# Shield_Programmer.net
KiCad netlist of a schematic drawn in EAGLE
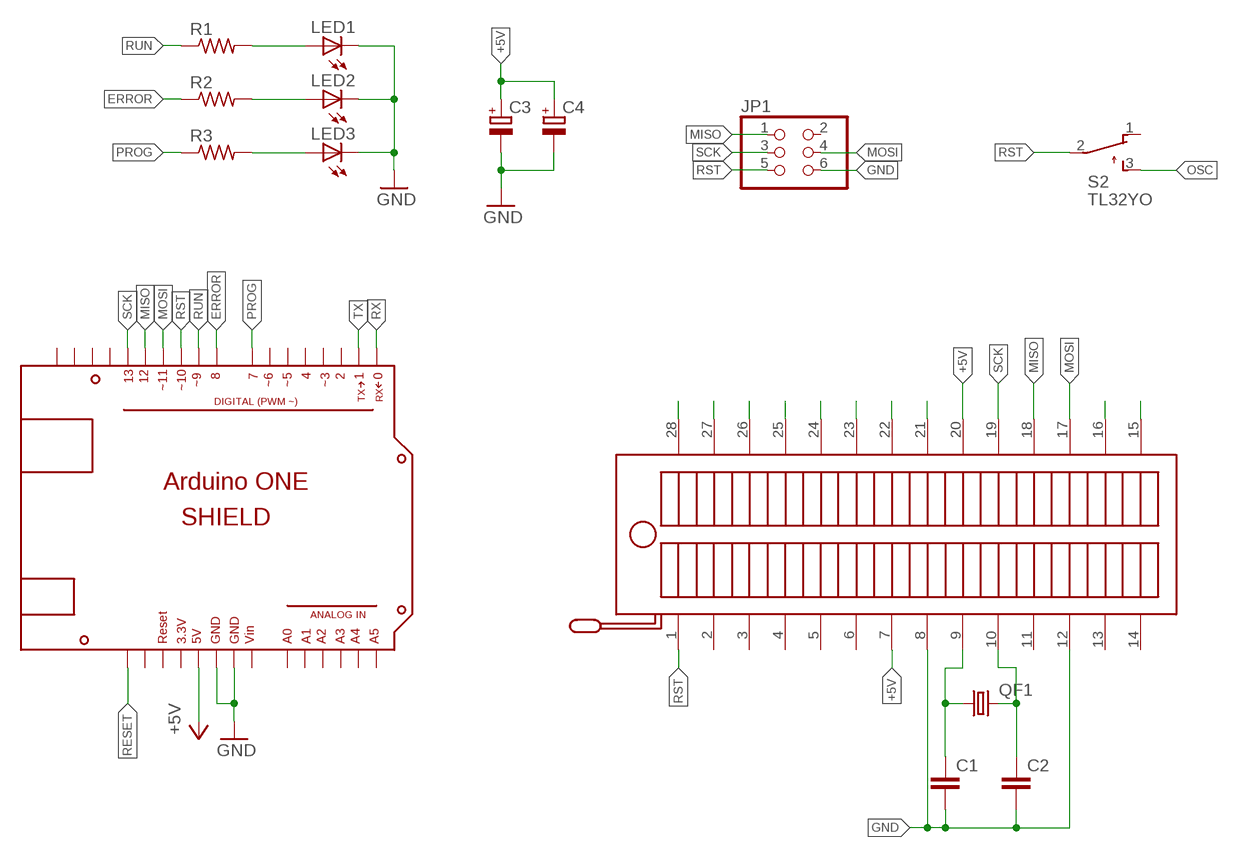
[diagram p0: schematic, sheet 1]

(export (version "E")
  (design (tool "Eeschema 10.0.6"))
  (components
    (comp (ref "C1")
      (value "C5/2.5")
      (footprint "eagle-import:C5B2.5")
      (libsource (lib "eagle-import") (part "C5/2.5"))
    )
    (comp (ref "C2")
      (value "C5/2.5")
      (footprint "eagle-import:C5B2.5")
      (libsource (lib "eagle-import") (part "C5/2.5"))
    )
    (comp (ref "C3")
      (value "CPOL-EUE2.5-7")
      (footprint "eagle-import:E2,5-7")
      (libsource (lib "eagle-import") (part "CPOL-EUE2.5-7"))
    )
    (comp (ref "C4")
      (value "CPOL-EUE2.5-7")
      (footprint "eagle-import:E2,5-7")
      (libsource (lib "eagle-import") (part "CPOL-EUE2.5-7"))
    )
    (comp (ref "JP1")
      (value "PINHD-2X3")
      (footprint "eagle-import:2X03")
      (libsource (lib "eagle-import") (part "PINHD-2X3"))
    )
    (comp (ref "LED1")
      (value "LED3MM")
      (footprint "eagle-import:LED3MM")
      (libsource (lib "eagle-import") (part "LED3MM"))
    )
    (comp (ref "LED2")
      (value "LED3MM")
      (footprint "eagle-import:LED3MM")
      (libsource (lib "eagle-import") (part "LED3MM"))
    )
    (comp (ref "LED3")
      (value "LED3MM")
      (footprint "eagle-import:LED3MM")
      (libsource (lib "eagle-import") (part "LED3MM"))
    )
    (comp (ref "QF1")
      (value "CRYSTALHC49U-V")
      (footprint "eagle-import:HC49U-V")
      (fields (field (name "OC_FARNELL") "1666969"))
      (libsource (lib "eagle-import") (part "CRYSTALHC49U-V"))
    )
    (comp (ref "R1")
      (value "R-US_0204/7")
      (footprint "eagle-import:0204_7")
      (libsource (lib "eagle-import") (part "R-US_0204/7"))
    )
    (comp (ref "R2")
      (value "R-US_0204/7")
      (footprint "eagle-import:0204_7")
      (libsource (lib "eagle-import") (part "R-US_0204/7"))
    )
    (comp (ref "R3")
      (value "R-US_0204/7")
      (footprint "eagle-import:0204_7")
      (libsource (lib "eagle-import") (part "R-US_0204/7"))
    )
    (comp (ref "S2")
      (value "TL32YO")
      (footprint "eagle-import:TL3XYO")
      (libsource (lib "eagle-import") (part "TL32YO"))
    )
    (comp (ref "U$2")
      (value "ZIF-28")
      (footprint "eagle-import:ZIF-28")
      (libsource (lib "eagle-import") (part "ZIF-28"))
    )
    (comp (ref "U$3")
      (value "SHIELD")
      (footprint "eagle-import:SHIELD")
      (libsource (lib "eagle-import") (part "SHIELD"))
    )
  )
  (nets
    (net (code "1") (name "+5V") (class "Default")
      (node (ref "C3") (pin "+") (pinfunction "+_+") (pintype "passive"))
      (node (ref "C4") (pin "+") (pinfunction "+_+") (pintype "passive"))
      (node (ref "U$2") (pin "20") (pinfunction "PIN20_20") (pintype "bidirectional"))
      (node (ref "U$2") (pin "7") (pinfunction "PIN7_7") (pintype "bidirectional"))
      (node (ref "U$3") (pin "5V") (pinfunction "5V_5V") (pintype "bidirectional"))
    )
    (net (code "2") (name "ERROR") (class "Default")
      (node (ref "R2") (pin "1") (pinfunction "1_1") (pintype "passive"))
      (node (ref "U$3") (pin "8") (pinfunction "8_8") (pintype "bidirectional"))
    )
    (net (code "3") (name "GND") (class "Default")
      (node (ref "C1") (pin "2") (pinfunction "2_2") (pintype "passive"))
      (node (ref "C2") (pin "2") (pinfunction "2_2") (pintype "passive"))
      (node (ref "C3") (pin "-") (pinfunction "-_-") (pintype "passive"))
      (node (ref "C4") (pin "-") (pinfunction "-_-") (pintype "passive"))
      (node (ref "JP1") (pin "6") (pinfunction "6_6") (pintype "passive"))
      (node (ref "LED1") (pin "K") (pinfunction "C_K") (pintype "passive"))
      (node (ref "LED2") (pin "K") (pinfunction "C_K") (pintype "passive"))
      (node (ref "LED3") (pin "K") (pinfunction "C_K") (pintype "passive"))
      (node (ref "U$2") (pin "12") (pinfunction "PIN12_12") (pintype "bidirectional"))
      (node (ref "U$2") (pin "8") (pinfunction "PIN8_8") (pintype "bidirectional"))
      (node (ref "U$3") (pin "GND1") (pinfunction "GND1_GND1") (pintype "bidirectional"))
      (node (ref "U$3") (pin "GND2") (pinfunction "GND2_GND2") (pintype "bidirectional"))
    )
    (net (code "4") (name "MISO") (class "Default")
      (node (ref "JP1") (pin "1") (pinfunction "1_1") (pintype "passive"))
      (node (ref "U$2") (pin "18") (pinfunction "PIN18_18") (pintype "bidirectional"))
      (node (ref "U$3") (pin "12") (pinfunction "12_12") (pintype "bidirectional"))
    )
    (net (code "5") (name "MOSI") (class "Default")
      (node (ref "JP1") (pin "4") (pinfunction "4_4") (pintype "passive"))
      (node (ref "U$2") (pin "17") (pinfunction "PIN17_17") (pintype "bidirectional"))
      (node (ref "U$3") (pin "11") (pinfunction "11_11") (pintype "bidirectional"))
    )
    (net (code "6") (name "Net-(LED1-PadA)") (class "Default")
      (node (ref "LED1") (pin "A") (pinfunction "A_A") (pintype "passive"))
      (node (ref "R1") (pin "2") (pinfunction "2_2") (pintype "passive"))
    )
    (net (code "7") (name "Net-(LED2-PadA)") (class "Default")
      (node (ref "LED2") (pin "A") (pinfunction "A_A") (pintype "passive"))
      (node (ref "R2") (pin "2") (pinfunction "2_2") (pintype "passive"))
    )
    (net (code "8") (name "Net-(LED3-PadA)") (class "Default")
      (node (ref "LED3") (pin "A") (pinfunction "A_A") (pintype "passive"))
      (node (ref "R3") (pin "2") (pinfunction "2_2") (pintype "passive"))
    )
    (net (code "9") (name "Net-(U$2-PIN10)") (class "Default")
      (node (ref "C2") (pin "1") (pinfunction "1_1") (pintype "passive"))
      (node (ref "QF1") (pin "2") (pinfunction "2_2") (pintype "passive"))
      (node (ref "U$2") (pin "10") (pinfunction "PIN10_10") (pintype "bidirectional"))
    )
    (net (code "10") (name "OSC") (class "Default")
      (node (ref "C1") (pin "1") (pinfunction "1_1") (pintype "passive"))
      (node (ref "QF1") (pin "1") (pinfunction "1_1") (pintype "passive"))
      (node (ref "S2") (pin "3") (pinfunction "S_3") (pintype "passive"))
      (node (ref "U$2") (pin "9") (pinfunction "PIN9_9") (pintype "bidirectional"))
    )
    (net (code "11") (name "PROG") (class "Default")
      (node (ref "R3") (pin "1") (pinfunction "1_1") (pintype "passive"))
      (node (ref "U$3") (pin "7") (pinfunction "7_7") (pintype "bidirectional"))
    )
    (net (code "12") (name "RESET") (class "Default")
      (node (ref "U$3") (pin "NONE") (pinfunction "NONE_NONE") (pintype "bidirectional"))
    )
    (net (code "13") (name "RST") (class "Default")
      (node (ref "JP1") (pin "5") (pinfunction "5_5") (pintype "passive"))
      (node (ref "S2") (pin "2") (pinfunction "P_2") (pintype "passive"))
      (node (ref "U$2") (pin "1") (pinfunction "PIN1_1") (pintype "bidirectional"))
      (node (ref "U$3") (pin "10") (pinfunction "10_10") (pintype "bidirectional"))
    )
    (net (code "14") (name "RUN") (class "Default")
      (node (ref "R1") (pin "1") (pinfunction "1_1") (pintype "passive"))
      (node (ref "U$3") (pin "9") (pinfunction "9_9") (pintype "bidirectional"))
    )
    (net (code "15") (name "RX") (class "Default")
      (node (ref "U$3") (pin "0") (pinfunction "0_0") (pintype "bidirectional"))
    )
    (net (code "16") (name "SCK") (class "Default")
      (node (ref "JP1") (pin "3") (pinfunction "3_3") (pintype "passive"))
      (node (ref "U$2") (pin "19") (pinfunction "PIN19_19") (pintype "bidirectional"))
      (node (ref "U$3") (pin "13") (pinfunction "13_13") (pintype "bidirectional"))
    )
    (net (code "17") (name "TX") (class "Default")
      (node (ref "U$3") (pin "1") (pinfunction "1_1") (pintype "bidirectional"))
    )
    (net (code "18") (name "unconnected-(JP1-Pad2)") (class "Default")
      (node (ref "JP1") (pin "2") (pinfunction "2_2") (pintype "passive"))
    )
    (net (code "19") (name "unconnected-(S2-O-Pad1)") (class "Default")
      (node (ref "S2") (pin "1") (pinfunction "O_1") (pintype "passive"))
    )
    (net (code "20") (name "unconnected-(U$2-PIN2-Pad2)") (class "Default")
      (node (ref "U$2") (pin "2") (pinfunction "PIN2_2") (pintype "bidirectional"))
    )
    (net (code "21") (name "unconnected-(U$2-PIN3-Pad3)") (class "Default")
      (node (ref "U$2") (pin "3") (pinfunction "PIN3_3") (pintype "bidirectional"))
    )
    (net (code "22") (name "unconnected-(U$2-PIN4-Pad4)") (class "Default")
      (node (ref "U$2") (pin "4") (pinfunction "PIN4_4") (pintype "bidirectional"))
    )
    (net (code "23") (name "unconnected-(U$2-PIN5-Pad5)") (class "Default")
      (node (ref "U$2") (pin "5") (pinfunction "PIN5_5") (pintype "bidirectional"))
    )
    (net (code "24") (name "unconnected-(U$2-PIN6-Pad6)") (class "Default")
      (node (ref "U$2") (pin "6") (pinfunction "PIN6_6") (pintype "bidirectional"))
    )
    (net (code "25") (name "unconnected-(U$2-PIN11-Pad11)") (class "Default")
      (node (ref "U$2") (pin "11") (pinfunction "PIN11_11") (pintype "bidirectional"))
    )
    (net (code "26") (name "unconnected-(U$2-PIN13-Pad13)") (class "Default")
      (node (ref "U$2") (pin "13") (pinfunction "PIN13_13") (pintype "bidirectional"))
    )
    (net (code "27") (name "unconnected-(U$2-PIN14-Pad14)") (class "Default")
      (node (ref "U$2") (pin "14") (pinfunction "PIN14_14") (pintype "bidirectional"))
    )
    (net (code "28") (name "unconnected-(U$2-PIN15-Pad15)") (class "Default")
      (node (ref "U$2") (pin "15") (pinfunction "PIN15_15") (pintype "bidirectional"))
    )
    (net (code "29") (name "unconnected-(U$2-PIN16-Pad16)") (class "Default")
      (node (ref "U$2") (pin "16") (pinfunction "PIN16_16") (pintype "bidirectional"))
    )
    (net (code "30") (name "unconnected-(U$2-PIN21-Pad21)") (class "Default")
      (node (ref "U$2") (pin "21") (pinfunction "PIN21_21") (pintype "bidirectional"))
    )
    (net (code "31") (name "unconnected-(U$2-PIN22-Pad22)") (class "Default")
      (node (ref "U$2") (pin "22") (pinfunction "PIN22_22") (pintype "bidirectional"))
    )
    (net (code "32") (name "unconnected-(U$2-PIN23-Pad23)") (class "Default")
      (node (ref "U$2") (pin "23") (pinfunction "PIN23_23") (pintype "bidirectional"))
    )
    (net (code "33") (name "unconnected-(U$2-PIN24-Pad24)") (class "Default")
      (node (ref "U$2") (pin "24") (pinfunction "PIN24_24") (pintype "bidirectional"))
    )
    (net (code "34") (name "unconnected-(U$2-PIN25-Pad25)") (class "Default")
      (node (ref "U$2") (pin "25") (pinfunction "PIN25_25") (pintype "bidirectional"))
    )
    (net (code "35") (name "unconnected-(U$2-PIN26-Pad26)") (class "Default")
      (node (ref "U$2") (pin "26") (pinfunction "PIN26_26") (pintype "bidirectional"))
    )
    (net (code "36") (name "unconnected-(U$2-PIN27-Pad27)") (class "Default")
      (node (ref "U$2") (pin "27") (pinfunction "PIN27_27") (pintype "bidirectional"))
    )
    (net (code "37") (name "unconnected-(U$2-PIN28-Pad28)") (class "Default")
      (node (ref "U$2") (pin "28") (pinfunction "PIN28_28") (pintype "bidirectional"))
    )
    (net (code "38") (name "unconnected-(U$3-Pad2)") (class "Default")
      (node (ref "U$3") (pin "2") (pinfunction "2_2") (pintype "bidirectional"))
    )
    (net (code "39") (name "unconnected-(U$3-Pad3)") (class "Default")
      (node (ref "U$3") (pin "3") (pinfunction "3_3") (pintype "bidirectional"))
    )
    (net (code "40") (name "unconnected-(U$3-Pad3.3V)") (class "Default")
      (node (ref "U$3") (pin "3.3V") (pinfunction "3.3V_3.3V") (pintype "bidirectional"))
    )
    (net (code "41") (name "unconnected-(U$3-Pad4)") (class "Default")
      (node (ref "U$3") (pin "4") (pinfunction "4_4") (pintype "bidirectional"))
    )
    (net (code "42") (name "unconnected-(U$3-Pad5)") (class "Default")
      (node (ref "U$3") (pin "5") (pinfunction "5_5") (pintype "bidirectional"))
    )
    (net (code "43") (name "unconnected-(U$3-Pad6)") (class "Default")
      (node (ref "U$3") (pin "6") (pinfunction "6_6") (pintype "bidirectional"))
    )
    (net (code "44") (name "unconnected-(U$3-Pad14)") (class "Default")
      (node (ref "U$3") (pin "14") (pinfunction "14_14") (pintype "bidirectional"))
    )
    (net (code "45") (name "unconnected-(U$3-Pad15)") (class "Default")
      (node (ref "U$3") (pin "15") (pinfunction "15_15") (pintype "bidirectional"))
    )
    (net (code "46") (name "unconnected-(U$3-Pad16)") (class "Default")
      (node (ref "U$3") (pin "16") (pinfunction "16_16") (pintype "bidirectional"))
    )
    (net (code "47") (name "unconnected-(U$3-Pad17)") (class "Default")
      (node (ref "U$3") (pin "17") (pinfunction "17_17") (pintype "bidirectional"))
    )
    (net (code "48") (name "unconnected-(U$3-PadA0)") (class "Default")
      (node (ref "U$3") (pin "A0") (pinfunction "A0_A0") (pintype "bidirectional"))
    )
    (net (code "49") (name "unconnected-(U$3-PadA1)") (class "Default")
      (node (ref "U$3") (pin "A1") (pinfunction "A1_A1") (pintype "bidirectional"))
    )
    (net (code "50") (name "unconnected-(U$3-PadA2)") (class "Default")
      (node (ref "U$3") (pin "A2") (pinfunction "A2_A2") (pintype "bidirectional"))
    )
    (net (code "51") (name "unconnected-(U$3-PadA3)") (class "Default")
      (node (ref "U$3") (pin "A3") (pinfunction "A3_A3") (pintype "bidirectional"))
    )
    (net (code "52") (name "unconnected-(U$3-PadA4)") (class "Default")
      (node (ref "U$3") (pin "A4") (pinfunction "A4_A4") (pintype "bidirectional"))
    )
    (net (code "53") (name "unconnected-(U$3-PadA5)") (class "Default")
      (node (ref "U$3") (pin "A5") (pinfunction "A5_A5") (pintype "bidirectional"))
    )
    (net (code "54") (name "unconnected-(U$3-PadIOREF)") (class "Default")
      (node (ref "U$3") (pin "IOREF") (pinfunction "IOREF_IOREF") (pintype "bidirectional"))
    )
    (net (code "55") (name "unconnected-(U$3-PadRST)") (class "Default")
      (node (ref "U$3") (pin "RST") (pinfunction "RST_RST") (pintype "bidirectional"))
    )
    (net (code "56") (name "unconnected-(U$3-PadVIN)") (class "Default")
      (node (ref "U$3") (pin "VIN") (pinfunction "VIN_VIN") (pintype "bidirectional"))
    )
  )
)
